# USB_OUT_B.net
KiCad netlist of a schematic drawn in Altium Designer
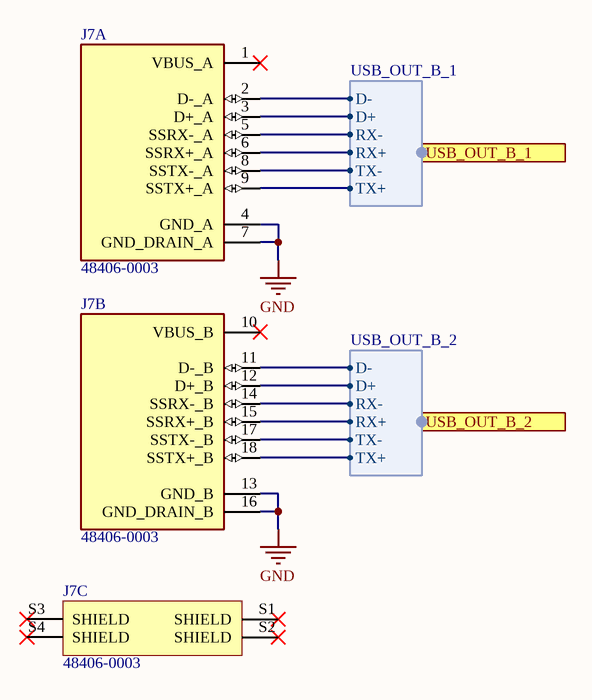
[diagram p0: USB_OUT_B.SchDoc]

(export (version "E")
  (design (tool "Eeschema 10.0.6"))
  (components
    (comp (ref "J7")
      (value "48406-0003")
      (footprint "MOLEX_48406")
      (fields (field (name "MF") "Molex"))
      (libsource (lib "KVM Library") (part "48406-0003"))
    )
  )
  (nets
    (net (code "5") (name "GND") (class "Default")
      (node (ref "J7") (pin "13") (pinfunction "GND_B_13") (pintype "power_in"))
      (node (ref "J7") (pin "16") (pinfunction "GND_DRAIN_B_16") (pintype "power_in"))
      (node (ref "J7") (pin "4") (pinfunction "GND_A_4") (pintype "power_in"))
      (node (ref "J7") (pin "7") (pinfunction "GND_DRAIN_A_7") (pintype "power_in"))
    )
    (net (code "6") (name "unconnected-(J7A-D+_A-Pad3)") (class "Default")
      (node (ref "J7") (pin "3") (pinfunction "D+_A_3") (pintype "bidirectional"))
    )
    (net (code "7") (name "unconnected-(J7A-D-_A-Pad2)") (class "Default")
      (node (ref "J7") (pin "2") (pinfunction "D-_A_2") (pintype "bidirectional"))
    )
    (net (code "8") (name "unconnected-(J7A-SSRX+_A-Pad6)") (class "Default")
      (node (ref "J7") (pin "6") (pinfunction "SSRX+_A_6") (pintype "bidirectional"))
    )
    (net (code "9") (name "unconnected-(J7A-SSRX-_A-Pad5)") (class "Default")
      (node (ref "J7") (pin "5") (pinfunction "SSRX-_A_5") (pintype "bidirectional"))
    )
    (net (code "10") (name "unconnected-(J7A-SSTX+_A-Pad9)") (class "Default")
      (node (ref "J7") (pin "9") (pinfunction "SSTX+_A_9") (pintype "bidirectional"))
    )
    (net (code "11") (name "unconnected-(J7A-SSTX-_A-Pad8)") (class "Default")
      (node (ref "J7") (pin "8") (pinfunction "SSTX-_A_8") (pintype "bidirectional"))
    )
    (net (code "12") (name "unconnected-(J7A-VBUS_A-Pad1)") (class "Default")
      (node (ref "J7") (pin "1") (pinfunction "VBUS_A_1") (pintype "power_in+no_connect"))
    )
    (net (code "13") (name "unconnected-(J7B-D+_B-Pad12)") (class "Default")
      (node (ref "J7") (pin "12") (pinfunction "D+_B_12") (pintype "bidirectional"))
    )
    (net (code "14") (name "unconnected-(J7B-D-_B-Pad11)") (class "Default")
      (node (ref "J7") (pin "11") (pinfunction "D-_B_11") (pintype "bidirectional"))
    )
    (net (code "15") (name "unconnected-(J7B-SSRX+_B-Pad15)") (class "Default")
      (node (ref "J7") (pin "15") (pinfunction "SSRX+_B_15") (pintype "bidirectional"))
    )
    (net (code "16") (name "unconnected-(J7B-SSRX-_B-Pad14)") (class "Default")
      (node (ref "J7") (pin "14") (pinfunction "SSRX-_B_14") (pintype "bidirectional"))
    )
    (net (code "17") (name "unconnected-(J7B-SSTX+_B-Pad18)") (class "Default")
      (node (ref "J7") (pin "18") (pinfunction "SSTX+_B_18") (pintype "bidirectional"))
    )
    (net (code "18") (name "unconnected-(J7B-SSTX-_B-Pad17)") (class "Default")
      (node (ref "J7") (pin "17") (pinfunction "SSTX-_B_17") (pintype "bidirectional"))
    )
    (net (code "19") (name "unconnected-(J7B-VBUS_B-Pad10)") (class "Default")
      (node (ref "J7") (pin "10") (pinfunction "VBUS_B_10") (pintype "power_in+no_connect"))
    )
    (net (code "20") (name "unconnected-(J7C-SHIELD-PadS1)") (class "Default")
      (node (ref "J7") (pin "S1") (pinfunction "SHIELD_S1") (pintype "passive+no_connect"))
    )
    (net (code "21") (name "unconnected-(J7C-SHIELD-PadS2)") (class "Default")
      (node (ref "J7") (pin "S2") (pinfunction "SHIELD_S2") (pintype "passive+no_connect"))
    )
    (net (code "22") (name "unconnected-(J7C-SHIELD-PadS3)") (class "Default")
      (node (ref "J7") (pin "S3") (pinfunction "SHIELD_S3") (pintype "passive+no_connect"))
    )
    (net (code "23") (name "unconnected-(J7C-SHIELD-PadS4)") (class "Default")
      (node (ref "J7") (pin "S4") (pinfunction "SHIELD_S4") (pintype "passive+no_connect"))
    )
  )
)
